# MotorControl.net
KiCad netlist of a schematic drawn in Altium Designer
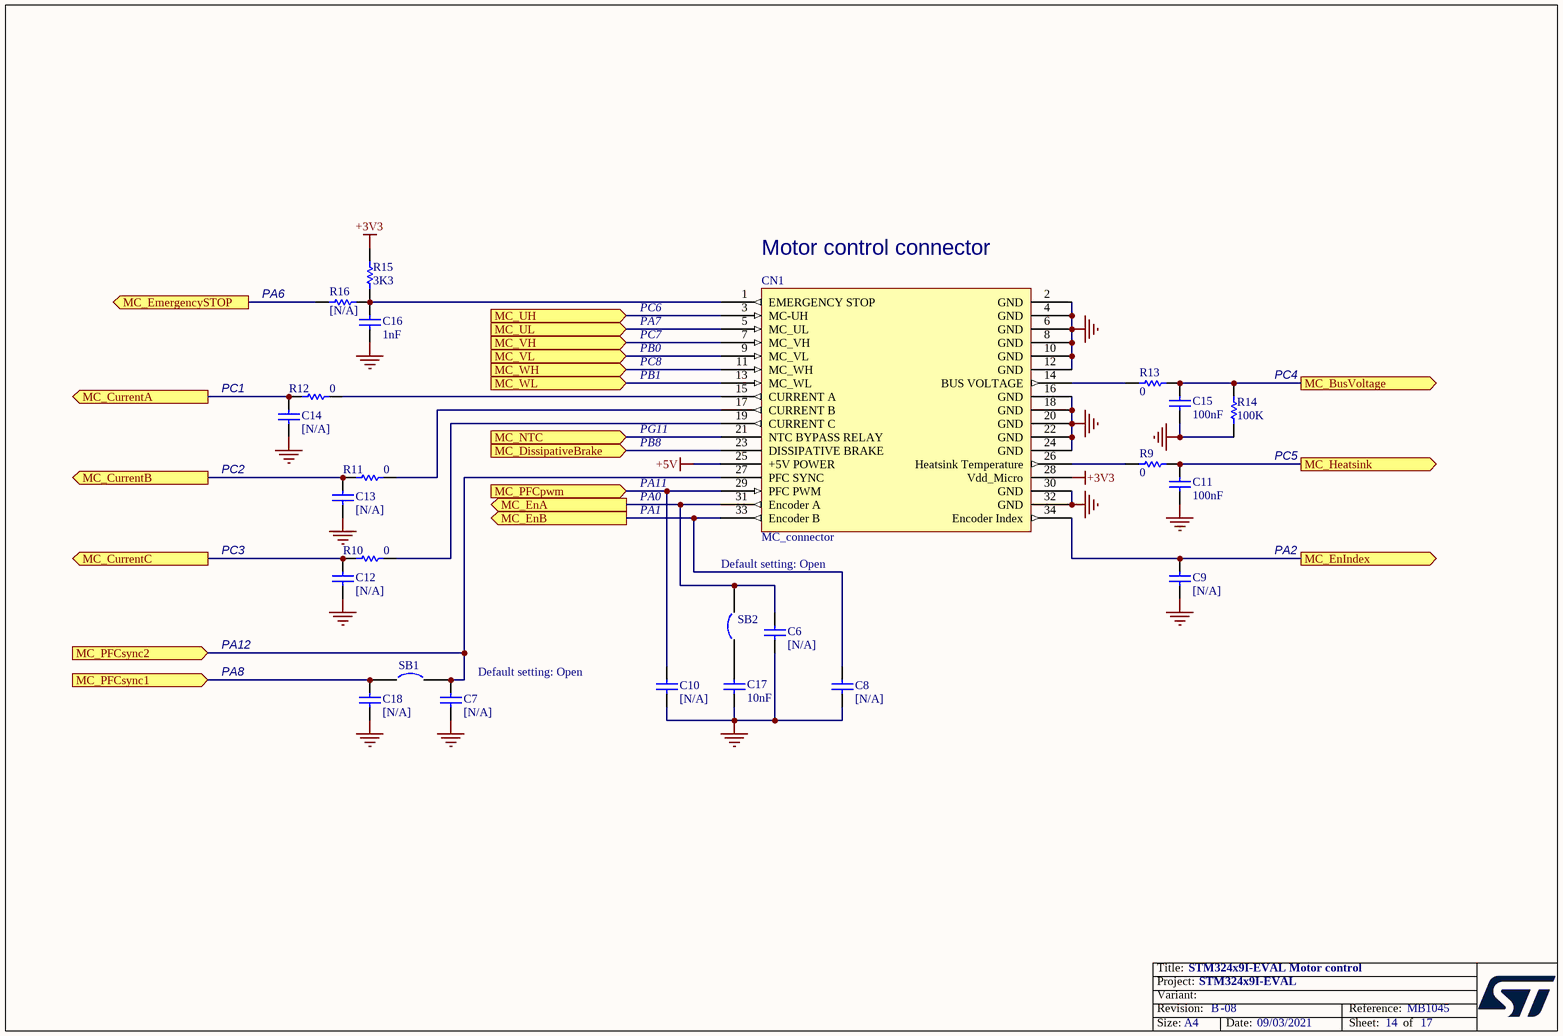
[diagram p0: MotorControl.SchDoc]

(export (version "E")
  (design (tool "Eeschema 10.0.6"))
  (components
    (comp (ref "C6")
      (value "[N/A]")
      (footprint "0603C")
      (description "Capacitor")
      (fields (field (name "PUBLISHER") "Altium Limited"))
      (libsource (lib "Miscellaneous Devices") (part "cap"))
    )
    (comp (ref "C7")
      (value "[N/A]")
      (footprint "0603C")
      (description "Capacitor")
      (fields (field (name "PUBLISHER") "Altium Limited"))
      (libsource (lib "Miscellaneous Devices") (part "cap"))
    )
    (comp (ref "C8")
      (value "[N/A]")
      (footprint "0603C")
      (description "Capacitor")
      (fields (field (name "PUBLISHER") "Altium Limited"))
      (libsource (lib "Miscellaneous Devices") (part "cap"))
    )
    (comp (ref "C9")
      (value "[N/A]")
      (footprint "0603C")
      (description "Capacitor")
      (fields (field (name "PUBLISHER") "Altium Limited"))
      (libsource (lib "Miscellaneous Devices") (part "cap"))
    )
    (comp (ref "C10")
      (value "[N/A]")
      (footprint "0603C")
      (description "Capacitor")
      (fields (field (name "PUBLISHER") "Altium Limited"))
      (libsource (lib "Miscellaneous Devices") (part "cap"))
    )
    (comp (ref "C11")
      (value "100nF")
      (footprint "0603C")
      (description "Capacitor")
      (fields (field (name "PUBLISHER") "Altium Limited"))
      (libsource (lib "Miscellaneous Devices") (part "Cap"))
    )
    (comp (ref "C12")
      (value "[N/A]")
      (footprint "0603C")
      (description "Capacitor")
      (fields (field (name "PUBLISHER") "Altium Limited"))
      (libsource (lib "Miscellaneous Devices") (part "cap"))
    )
    (comp (ref "C13")
      (value "[N/A]")
      (footprint "0603C")
      (description "Capacitor")
      (fields (field (name "PUBLISHER") "Altium Limited"))
      (libsource (lib "Miscellaneous Devices") (part "cap"))
    )
    (comp (ref "C14")
      (value "[N/A]")
      (footprint "0603C")
      (description "Capacitor")
      (fields (field (name "PUBLISHER") "Altium Limited"))
      (libsource (lib "Miscellaneous Devices") (part "cap"))
    )
    (comp (ref "C15")
      (value "100nF")
      (footprint "0603C")
      (description "Capacitor")
      (fields (field (name "PUBLISHER") "Altium Limited"))
      (libsource (lib "Miscellaneous Devices") (part "Cap"))
    )
    (comp (ref "C16")
      (value "1nF")
      (footprint "0603C")
      (description "Capacitor")
      (fields (field (name "PUBLISHER") "Altium Limited"))
      (libsource (lib "Miscellaneous Devices") (part "CAP"))
    )
    (comp (ref "C17")
      (value "10nF")
      (footprint "0603C")
      (description "Capacitor")
      (fields (field (name "PUBLISHER") "Altium Limited"))
      (libsource (lib "Miscellaneous Devices") (part "CAP"))
    )
    (comp (ref "C18")
      (value "[N/A]")
      (footprint "0603C")
      (description "Capacitor")
      (fields (field (name "PUBLISHER") "Altium Limited"))
      (libsource (lib "Miscellaneous Devices") (part "cap"))
    )
    (comp (ref "CN1")
      (value "MC_connector")
      (footprint "IDC34S")
      (libsource (lib "MB525") (part "MC_connector"))
    )
    (comp (ref "R9")
      (value "0")
      (footprint "0603R")
      (description "Resistor")
      (fields (field (name "PUBLISHER") "Altium Limited"))
      (libsource (lib "Miscellaneous Devices") (part "Res1"))
    )
    (comp (ref "R10")
      (value "0")
      (footprint "0603R")
      (description "Resistor")
      (fields (field (name "PUBLISHER") "Altium Limited"))
      (libsource (lib "Miscellaneous Devices") (part "Res1"))
    )
    (comp (ref "R11")
      (value "0")
      (footprint "0603R")
      (description "Resistor")
      (fields (field (name "PUBLISHER") "Altium Limited"))
      (libsource (lib "Miscellaneous Devices") (part "Res1"))
    )
    (comp (ref "R12")
      (value "0")
      (footprint "0603R")
      (description "Resistor")
      (fields (field (name "PUBLISHER") "Altium Limited"))
      (libsource (lib "Miscellaneous Devices") (part "Res1"))
    )
    (comp (ref "R13")
      (value "0")
      (footprint "0603R")
      (description "Resistor")
      (fields (field (name "PUBLISHER") "Altium Limited"))
      (libsource (lib "Miscellaneous Devices") (part "Res1"))
    )
    (comp (ref "R14")
      (value "100K")
      (footprint "0603R")
      (description "Resistor")
      (fields (field (name "PUBLISHER") "Altium Limited"))
      (libsource (lib "Miscellaneous Devices") (part "res1"))
    )
    (comp (ref "R15")
      (value "3K3")
      (footprint "0603R")
      (description "Resistor")
      (fields (field (name "PUBLISHER") "Altium Limited"))
      (libsource (lib "Miscellaneous Devices") (part "Res1"))
    )
    (comp (ref "R16")
      (value "[N/A]")
      (footprint "0603R")
      (description "Resistor")
      (fields (field (name "PUBLISHER") "Altium Limited"))
      (libsource (lib "Miscellaneous Devices") (part "Res1"))
    )
    (comp (ref "SB1")
      (value "~")
      (footprint "JP2_SMD")
      (description "Circuit Breaker")
      (fields (field (name "PUBLISHER") "Altium Limited"))
      (libsource (lib "Miscellaneous Devices") (part "Circuit Breaker"))
    )
    (comp (ref "SB2")
      (value "~")
      (footprint "JP2_SMD")
      (description "Circuit Breaker")
      (fields (field (name "PUBLISHER") "Altium Limited"))
      (libsource (lib "Miscellaneous Devices") (part "Circuit Breaker"))
    )
  )
  (nets
    (net (code "1") (name "+3V3") (class "Default")
      (node (ref "CN1") (pin "28") (pinfunction "Vdd_Micro_28") (pintype "power_in"))
      (node (ref "R15") (pin "2") (pinfunction "2_2") (pintype "passive"))
    )
    (net (code "2") (name "+5V") (class "Default")
      (node (ref "CN1") (pin "25") (pinfunction "+5V_POWER_25") (pintype "power_in"))
    )
    (net (code "3") (name "/MC_BusVoltage") (class "Default")
      (node (ref "C15") (pin "1") (pinfunction "1_1") (pintype "passive"))
      (node (ref "R13") (pin "2") (pinfunction "2_2") (pintype "passive"))
      (node (ref "R14") (pin "1") (pinfunction "1_1") (pintype "passive"))
    )
    (net (code "4") (name "/MC_CurrentA") (class "Default")
      (node (ref "C14") (pin "2") (pinfunction "2_2") (pintype "passive"))
      (node (ref "R12") (pin "1") (pinfunction "1_1") (pintype "passive"))
    )
    (net (code "5") (name "/MC_CurrentB") (class "Default")
      (node (ref "C13") (pin "2") (pinfunction "2_2") (pintype "passive"))
      (node (ref "R11") (pin "1") (pinfunction "1_1") (pintype "passive"))
    )
    (net (code "6") (name "/MC_CurrentC") (class "Default")
      (node (ref "C12") (pin "2") (pinfunction "2_2") (pintype "passive"))
      (node (ref "R10") (pin "1") (pinfunction "1_1") (pintype "passive"))
    )
    (net (code "7") (name "/MC_DissipativeBrake") (class "Default")
      (node (ref "CN1") (pin "23") (pinfunction "DISSIPATIVE_BRAKE_23") (pintype "passive"))
    )
    (net (code "8") (name "/MC_EmergencySTOP") (class "Default")
      (node (ref "R16") (pin "2") (pinfunction "2_2") (pintype "passive"))
    )
    (net (code "9") (name "/MC_EnA") (class "Default")
      (node (ref "C6") (pin "2") (pinfunction "2_2") (pintype "passive"))
      (node (ref "CN1") (pin "31") (pinfunction "Encoder_A_31") (pintype "output"))
      (node (ref "SB2") (pin "2") (pinfunction "2_2") (pintype "passive"))
    )
    (net (code "10") (name "/MC_EnB") (class "Default")
      (node (ref "C8") (pin "2") (pinfunction "2_2") (pintype "passive"))
      (node (ref "CN1") (pin "33") (pinfunction "Encoder_B_33") (pintype "output"))
    )
    (net (code "11") (name "/MC_EnIndex") (class "Default")
      (node (ref "C9") (pin "2") (pinfunction "2_2") (pintype "passive"))
      (node (ref "CN1") (pin "34") (pinfunction "Encoder_Index_34") (pintype "output"))
    )
    (net (code "12") (name "/MC_Heatsink") (class "Default")
      (node (ref "C11") (pin "1") (pinfunction "1_1") (pintype "passive"))
      (node (ref "R9") (pin "2") (pinfunction "2_2") (pintype "passive"))
    )
    (net (code "13") (name "/MC_NTC") (class "Default")
      (node (ref "CN1") (pin "21") (pinfunction "NTC_BYPASS_RELAY_21") (pintype "passive"))
    )
    (net (code "14") (name "/MC_PFCpwm") (class "Default")
      (node (ref "C10") (pin "2") (pinfunction "2_2") (pintype "passive"))
      (node (ref "CN1") (pin "29") (pinfunction "PFC_PWM_29") (pintype "input"))
    )
    (net (code "15") (name "/MC_PFCsync1") (class "Default")
      (node (ref "C18") (pin "2") (pinfunction "2_2") (pintype "passive"))
      (node (ref "SB1") (pin "1") (pinfunction "1_1") (pintype "passive"))
    )
    (net (code "16") (name "/MC_PFCsync2") (class "Default")
      (node (ref "C7") (pin "2") (pinfunction "2_2") (pintype "passive"))
      (node (ref "CN1") (pin "27") (pinfunction "PFC_SYNC_27") (pintype "passive"))
      (node (ref "SB1") (pin "2") (pinfunction "2_2") (pintype "passive"))
    )
    (net (code "17") (name "/MC_UH") (class "Default")
      (node (ref "CN1") (pin "3") (pinfunction "MC-UH_3") (pintype "input"))
    )
    (net (code "18") (name "/MC_UL") (class "Default")
      (node (ref "CN1") (pin "5") (pinfunction "MC_UL_5") (pintype "input"))
    )
    (net (code "19") (name "/MC_VH") (class "Default")
      (node (ref "CN1") (pin "7") (pinfunction "MC_VH_7") (pintype "input"))
    )
    (net (code "20") (name "/MC_VL") (class "Default")
      (node (ref "CN1") (pin "9") (pinfunction "MC_VL_9") (pintype "input"))
    )
    (net (code "21") (name "/MC_WH") (class "Default")
      (node (ref "CN1") (pin "11") (pinfunction "MC_WH_11") (pintype "input"))
    )
    (net (code "22") (name "/MC_WL") (class "Default")
      (node (ref "CN1") (pin "13") (pinfunction "MC_WL_13") (pintype "input"))
    )
    (net (code "23") (name "GND") (class "Default")
      (node (ref "C10") (pin "1") (pinfunction "1_1") (pintype "passive"))
      (node (ref "C11") (pin "2") (pinfunction "2_2") (pintype "passive"))
      (node (ref "C12") (pin "1") (pinfunction "1_1") (pintype "passive"))
      (node (ref "C13") (pin "1") (pinfunction "1_1") (pintype "passive"))
      (node (ref "C14") (pin "1") (pinfunction "1_1") (pintype "passive"))
      (node (ref "C15") (pin "2") (pinfunction "2_2") (pintype "passive"))
      (node (ref "C16") (pin "1") (pinfunction "1_1") (pintype "passive"))
      (node (ref "C17") (pin "2") (pinfunction "2_2") (pintype "passive"))
      (node (ref "C18") (pin "1") (pinfunction "1_1") (pintype "passive"))
      (node (ref "C6") (pin "1") (pinfunction "1_1") (pintype "passive"))
      (node (ref "C7") (pin "1") (pinfunction "1_1") (pintype "passive"))
      (node (ref "C8") (pin "1") (pinfunction "1_1") (pintype "passive"))
      (node (ref "C9") (pin "1") (pinfunction "1_1") (pintype "passive"))
      (node (ref "CN1") (pin "10") (pinfunction "GND_10") (pintype "power_in"))
      (node (ref "CN1") (pin "12") (pinfunction "GND_12") (pintype "power_in"))
      (node (ref "CN1") (pin "16") (pinfunction "GND_16") (pintype "power_in"))
      (node (ref "CN1") (pin "18") (pinfunction "GND_18") (pintype "power_in"))
      (node (ref "CN1") (pin "2") (pinfunction "GND_2") (pintype "power_in"))
      (node (ref "CN1") (pin "20") (pinfunction "GND_20") (pintype "power_in"))
      (node (ref "CN1") (pin "22") (pinfunction "GND_22") (pintype "power_in"))
      (node (ref "CN1") (pin "24") (pinfunction "GND_24") (pintype "power_in"))
      (node (ref "CN1") (pin "30") (pinfunction "GND_30") (pintype "power_in"))
      (node (ref "CN1") (pin "32") (pinfunction "GND_32") (pintype "power_in"))
      (node (ref "CN1") (pin "4") (pinfunction "GND_4") (pintype "power_in"))
      (node (ref "CN1") (pin "6") (pinfunction "GND_6") (pintype "power_in"))
      (node (ref "CN1") (pin "8") (pinfunction "GND_8") (pintype "power_in"))
      (node (ref "R14") (pin "2") (pinfunction "2_2") (pintype "passive"))
    )
    (net (code "24") (name "Net-(C17-Pad1)") (class "Default")
      (node (ref "C17") (pin "1") (pinfunction "1_1") (pintype "passive"))
      (node (ref "SB2") (pin "1") (pinfunction "1_1") (pintype "passive"))
    )
    (net (code "25") (name "Net-(CN1-BUS_VOLTAGE)") (class "Default")
      (node (ref "CN1") (pin "14") (pinfunction "BUS_VOLTAGE_14") (pintype "output"))
      (node (ref "R13") (pin "1") (pinfunction "1_1") (pintype "passive"))
    )
    (net (code "26") (name "Net-(CN1-CURRENT_A)") (class "Default")
      (node (ref "CN1") (pin "15") (pinfunction "CURRENT_A_15") (pintype "output"))
      (node (ref "R12") (pin "2") (pinfunction "2_2") (pintype "passive"))
    )
    (net (code "27") (name "Net-(CN1-CURRENT_B)") (class "Default")
      (node (ref "CN1") (pin "17") (pinfunction "CURRENT_B_17") (pintype "output"))
      (node (ref "R11") (pin "2") (pinfunction "2_2") (pintype "passive"))
    )
    (net (code "28") (name "Net-(CN1-CURRENT_C)") (class "Default")
      (node (ref "CN1") (pin "19") (pinfunction "CURRENT_C_19") (pintype "output"))
      (node (ref "R10") (pin "2") (pinfunction "2_2") (pintype "passive"))
    )
    (net (code "29") (name "Net-(CN1-EMERGENCY_STOP)") (class "Default")
      (node (ref "C16") (pin "2") (pinfunction "2_2") (pintype "passive"))
      (node (ref "CN1") (pin "1") (pinfunction "EMERGENCY_STOP_1") (pintype "output"))
      (node (ref "R15") (pin "1") (pinfunction "1_1") (pintype "passive"))
      (node (ref "R16") (pin "1") (pinfunction "1_1") (pintype "passive"))
    )
    (net (code "30") (name "Net-(CN1-Heatsink_Temperature)") (class "Default")
      (node (ref "CN1") (pin "26") (pinfunction "Heatsink_Temperature_26") (pintype "output"))
      (node (ref "R9") (pin "1") (pinfunction "1_1") (pintype "passive"))
    )
  )
)
